# wireless.net
KiCad netlist of a schematic drawn in Altium Designer
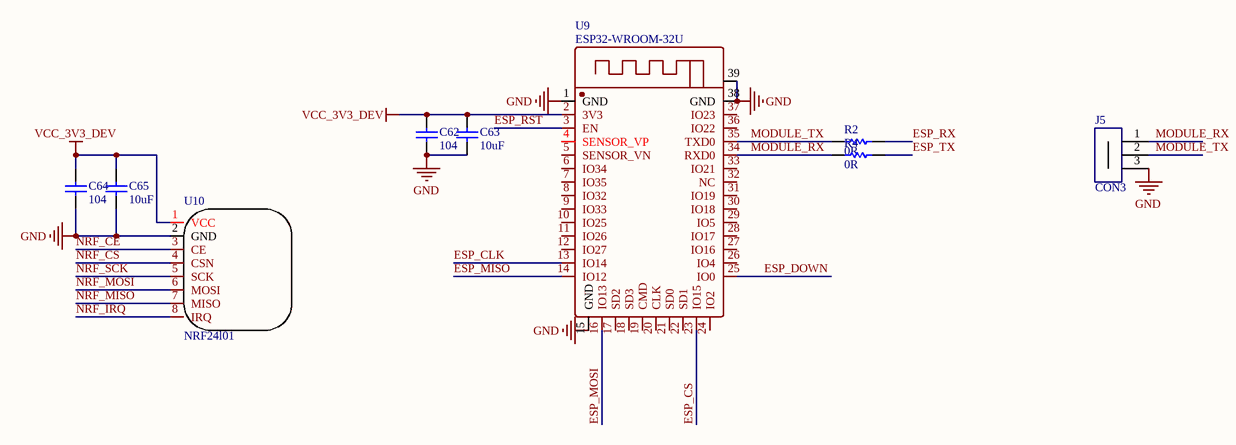
[diagram p0: wireless.SchDoc]

(export (version "E")
  (design (tool "Eeschema 10.0.6"))
  (components
    (comp (ref "C62") (value "104") (footprint "C 0603") (libsource (lib "Sheet") (part "CAP")))
    (comp (ref "C63") (value "10uF") (footprint "C 0603") (libsource (lib "Sheet") (part "CAP")))
    (comp (ref "C64") (value "104") (footprint "C 0603") (libsource (lib "Sheet") (part "CAP")))
    (comp (ref "C65") (value "10uF") (footprint "C 0603") (libsource (lib "Sheet") (part "CAP")))
    (comp (ref "J5") (value "CON3") (footprint "SMD_3P-1.25") (libsource (lib "Sheet") (part "CON3")))
    (comp (ref "R2") (value "0R") (footprint "R 0603") (libsource (lib "Sheet") (part "RES")))
    (comp (ref "R4") (value "0R") (footprint "R 0603") (libsource (lib "Sheet") (part "RES")))
    (comp (ref "U9")
      (value "ESP32-WROOM-32U")
      (footprint "ESP32-WROOM-32U")
      (libsource (lib "mylib") (part "ESP32-WROOM-32U"))
    )
    (comp (ref "U10") (value "NRF24l01") (footprint "NRF24l01") (libsource (lib "Sheet") (part "NRF24l01")))
  )
  (nets
    (net (code "1") (name "/ESP_CLK") (class "Default")
      (node (ref "U9") (pin "13") (pinfunction "IO14_13") (pintype "passive"))
    )
    (net (code "2") (name "/ESP_CS") (class "Default")
      (node (ref "U9") (pin "23") (pinfunction "IO15_23") (pintype "passive"))
    )
    (net (code "3") (name "/ESP_DOWN") (class "Default")
      (node (ref "U9") (pin "25") (pinfunction "IO0_25") (pintype "passive"))
    )
    (net (code "4") (name "/ESP_MISO") (class "Default")
      (node (ref "U9") (pin "14") (pinfunction "IO12_14") (pintype "passive"))
    )
    (net (code "5") (name "/ESP_MOSI") (class "Default")
      (node (ref "U9") (pin "16") (pinfunction "IO13_16") (pintype "passive"))
    )
    (net (code "6") (name "/ESP_RST") (class "Default")
      (node (ref "U9") (pin "3") (pinfunction "EN_3") (pintype "passive"))
    )
    (net (code "7") (name "/ESP_RX") (class "Default")
      (node (ref "R2") (pin "2") (pinfunction "2_2") (pintype "passive"))
    )
    (net (code "8") (name "/ESP_TX") (class "Default")
      (node (ref "R4") (pin "2") (pinfunction "2_2") (pintype "passive"))
    )
    (net (code "9") (name "/MODULE_RX") (class "Default")
      (node (ref "J5") (pin "1") (pinfunction "1_1") (pintype "passive"))
      (node (ref "R4") (pin "1") (pinfunction "1_1") (pintype "passive"))
      (node (ref "U9") (pin "34") (pinfunction "RXD0_34") (pintype "passive"))
    )
    (net (code "10") (name "/MODULE_TX") (class "Default")
      (node (ref "J5") (pin "2") (pinfunction "2_2") (pintype "passive"))
      (node (ref "R2") (pin "1") (pinfunction "1_1") (pintype "passive"))
      (node (ref "U9") (pin "35") (pinfunction "TXD0_35") (pintype "passive"))
    )
    (net (code "11") (name "/NRF_CE") (class "Default")
      (node (ref "U10") (pin "3") (pinfunction "CE_3") (pintype "passive"))
    )
    (net (code "12") (name "/NRF_CS") (class "Default")
      (node (ref "U10") (pin "4") (pinfunction "CSN_4") (pintype "passive"))
    )
    (net (code "13") (name "/NRF_IRQ") (class "Default")
      (node (ref "U10") (pin "8") (pinfunction "IRQ_8") (pintype "passive"))
    )
    (net (code "14") (name "/NRF_MISO") (class "Default")
      (node (ref "U10") (pin "7") (pinfunction "MISO_7") (pintype "passive"))
    )
    (net (code "15") (name "/NRF_MOSI") (class "Default")
      (node (ref "U10") (pin "6") (pinfunction "MOSI_6") (pintype "passive"))
    )
    (net (code "16") (name "/NRF_SCK") (class "Default")
      (node (ref "U10") (pin "5") (pinfunction "SCK_5") (pintype "passive"))
    )
    (net (code "17") (name "GND") (class "Default")
      (node (ref "C62") (pin "2") (pinfunction "2_2") (pintype "passive"))
      (node (ref "C63") (pin "2") (pinfunction "2_2") (pintype "passive"))
      (node (ref "C64") (pin "2") (pinfunction "2_2") (pintype "passive"))
      (node (ref "C65") (pin "2") (pinfunction "2_2") (pintype "passive"))
      (node (ref "J5") (pin "3") (pinfunction "3_3") (pintype "passive"))
      (node (ref "U10") (pin "2") (pinfunction "GND_2") (pintype "passive"))
      (node (ref "U9") (pin "1") (pinfunction "GND_1") (pintype "passive"))
      (node (ref "U9") (pin "15") (pinfunction "GND_15") (pintype "passive"))
      (node (ref "U9") (pin "38") (pinfunction "GND_38") (pintype "passive"))
      (node (ref "U9") (pin "39") (pinfunction "GND_39") (pintype "passive"))
    )
    (net (code "18") (name "VCC_3V3_DEV") (class "Default")
      (node (ref "C62") (pin "1") (pinfunction "1_1") (pintype "passive"))
      (node (ref "C63") (pin "1") (pinfunction "1_1") (pintype "passive"))
      (node (ref "C64") (pin "1") (pinfunction "1_1") (pintype "passive"))
      (node (ref "C65") (pin "1") (pinfunction "1_1") (pintype "passive"))
      (node (ref "U10") (pin "1") (pinfunction "VCC_1") (pintype "passive"))
      (node (ref "U9") (pin "2") (pinfunction "3V3_2") (pintype "passive"))
    )
    (net (code "19") (name "unconnected-(U9-CLK-Pad20)") (class "Default")
      (node (ref "U9") (pin "20") (pinfunction "CLK_20") (pintype "passive"))
    )
    (net (code "20") (name "unconnected-(U9-CMD-Pad19)") (class "Default")
      (node (ref "U9") (pin "19") (pinfunction "CMD_19") (pintype "passive"))
    )
    (net (code "21") (name "unconnected-(U9-IO2-Pad24)") (class "Default")
      (node (ref "U9") (pin "24") (pinfunction "IO2_24") (pintype "passive"))
    )
    (net (code "22") (name "unconnected-(U9-IO4-Pad26)") (class "Default")
      (node (ref "U9") (pin "26") (pinfunction "IO4_26") (pintype "passive"))
    )
    (net (code "23") (name "unconnected-(U9-IO5-Pad29)") (class "Default")
      (node (ref "U9") (pin "29") (pinfunction "IO5_29") (pintype "passive"))
    )
    (net (code "24") (name "unconnected-(U9-IO16-Pad27)") (class "Default")
      (node (ref "U9") (pin "27") (pinfunction "IO16_27") (pintype "passive"))
    )
    (net (code "25") (name "unconnected-(U9-IO17-Pad28)") (class "Default")
      (node (ref "U9") (pin "28") (pinfunction "IO17_28") (pintype "passive"))
    )
    (net (code "26") (name "unconnected-(U9-IO18-Pad30)") (class "Default")
      (node (ref "U9") (pin "30") (pinfunction "IO18_30") (pintype "passive"))
    )
    (net (code "27") (name "unconnected-(U9-IO19-Pad31)") (class "Default")
      (node (ref "U9") (pin "31") (pinfunction "IO19_31") (pintype "passive"))
    )
    (net (code "28") (name "unconnected-(U9-IO21-Pad33)") (class "Default")
      (node (ref "U9") (pin "33") (pinfunction "IO21_33") (pintype "passive"))
    )
    (net (code "29") (name "unconnected-(U9-IO22-Pad36)") (class "Default")
      (node (ref "U9") (pin "36") (pinfunction "IO22_36") (pintype "passive"))
    )
    (net (code "30") (name "unconnected-(U9-IO23-Pad37)") (class "Default")
      (node (ref "U9") (pin "37") (pinfunction "IO23_37") (pintype "passive"))
    )
    (net (code "31") (name "unconnected-(U9-IO25-Pad10)") (class "Default")
      (node (ref "U9") (pin "10") (pinfunction "IO25_10") (pintype "passive"))
    )
    (net (code "32") (name "unconnected-(U9-IO26-Pad11)") (class "Default")
      (node (ref "U9") (pin "11") (pinfunction "IO26_11") (pintype "passive"))
    )
    (net (code "33") (name "unconnected-(U9-IO27-Pad12)") (class "Default")
      (node (ref "U9") (pin "12") (pinfunction "IO27_12") (pintype "passive"))
    )
    (net (code "34") (name "unconnected-(U9-IO32-Pad8)") (class "Default")
      (node (ref "U9") (pin "8") (pinfunction "IO32_8") (pintype "passive"))
    )
    (net (code "35") (name "unconnected-(U9-IO33-Pad9)") (class "Default")
      (node (ref "U9") (pin "9") (pinfunction "IO33_9") (pintype "passive"))
    )
    (net (code "36") (name "unconnected-(U9-IO34-Pad6)") (class "Default")
      (node (ref "U9") (pin "6") (pinfunction "IO34_6") (pintype "passive"))
    )
    (net (code "37") (name "unconnected-(U9-IO35-Pad7)") (class "Default")
      (node (ref "U9") (pin "7") (pinfunction "IO35_7") (pintype "passive"))
    )
    (net (code "38") (name "unconnected-(U9-NC-Pad32)") (class "Default")
      (node (ref "U9") (pin "32") (pinfunction "NC_32") (pintype "passive"))
    )
    (net (code "39") (name "unconnected-(U9-SD0-Pad21)") (class "Default")
      (node (ref "U9") (pin "21") (pinfunction "SD0_21") (pintype "passive"))
    )
    (net (code "40") (name "unconnected-(U9-SD1-Pad22)") (class "Default")
      (node (ref "U9") (pin "22") (pinfunction "SD1_22") (pintype "passive"))
    )
    (net (code "41") (name "unconnected-(U9-SD2-Pad17)") (class "Default")
      (node (ref "U9") (pin "17") (pinfunction "SD2_17") (pintype "passive"))
    )
    (net (code "42") (name "unconnected-(U9-SD3-Pad18)") (class "Default")
      (node (ref "U9") (pin "18") (pinfunction "SD3_18") (pintype "passive"))
    )
    (net (code "43") (name "unconnected-(U9-SENSOR_VN-Pad5)") (class "Default")
      (node (ref "U9") (pin "5") (pinfunction "SENSOR_VN_5") (pintype "passive"))
    )
    (net (code "44") (name "unconnected-(U9-SENSOR_VP-Pad4)") (class "Default")
      (node (ref "U9") (pin "4") (pinfunction "SENSOR_VP_4") (pintype "passive"))
    )
  )
)
